# Voicecard-SMRMU-v01.net
KiCad netlist of a schematic drawn in EAGLE
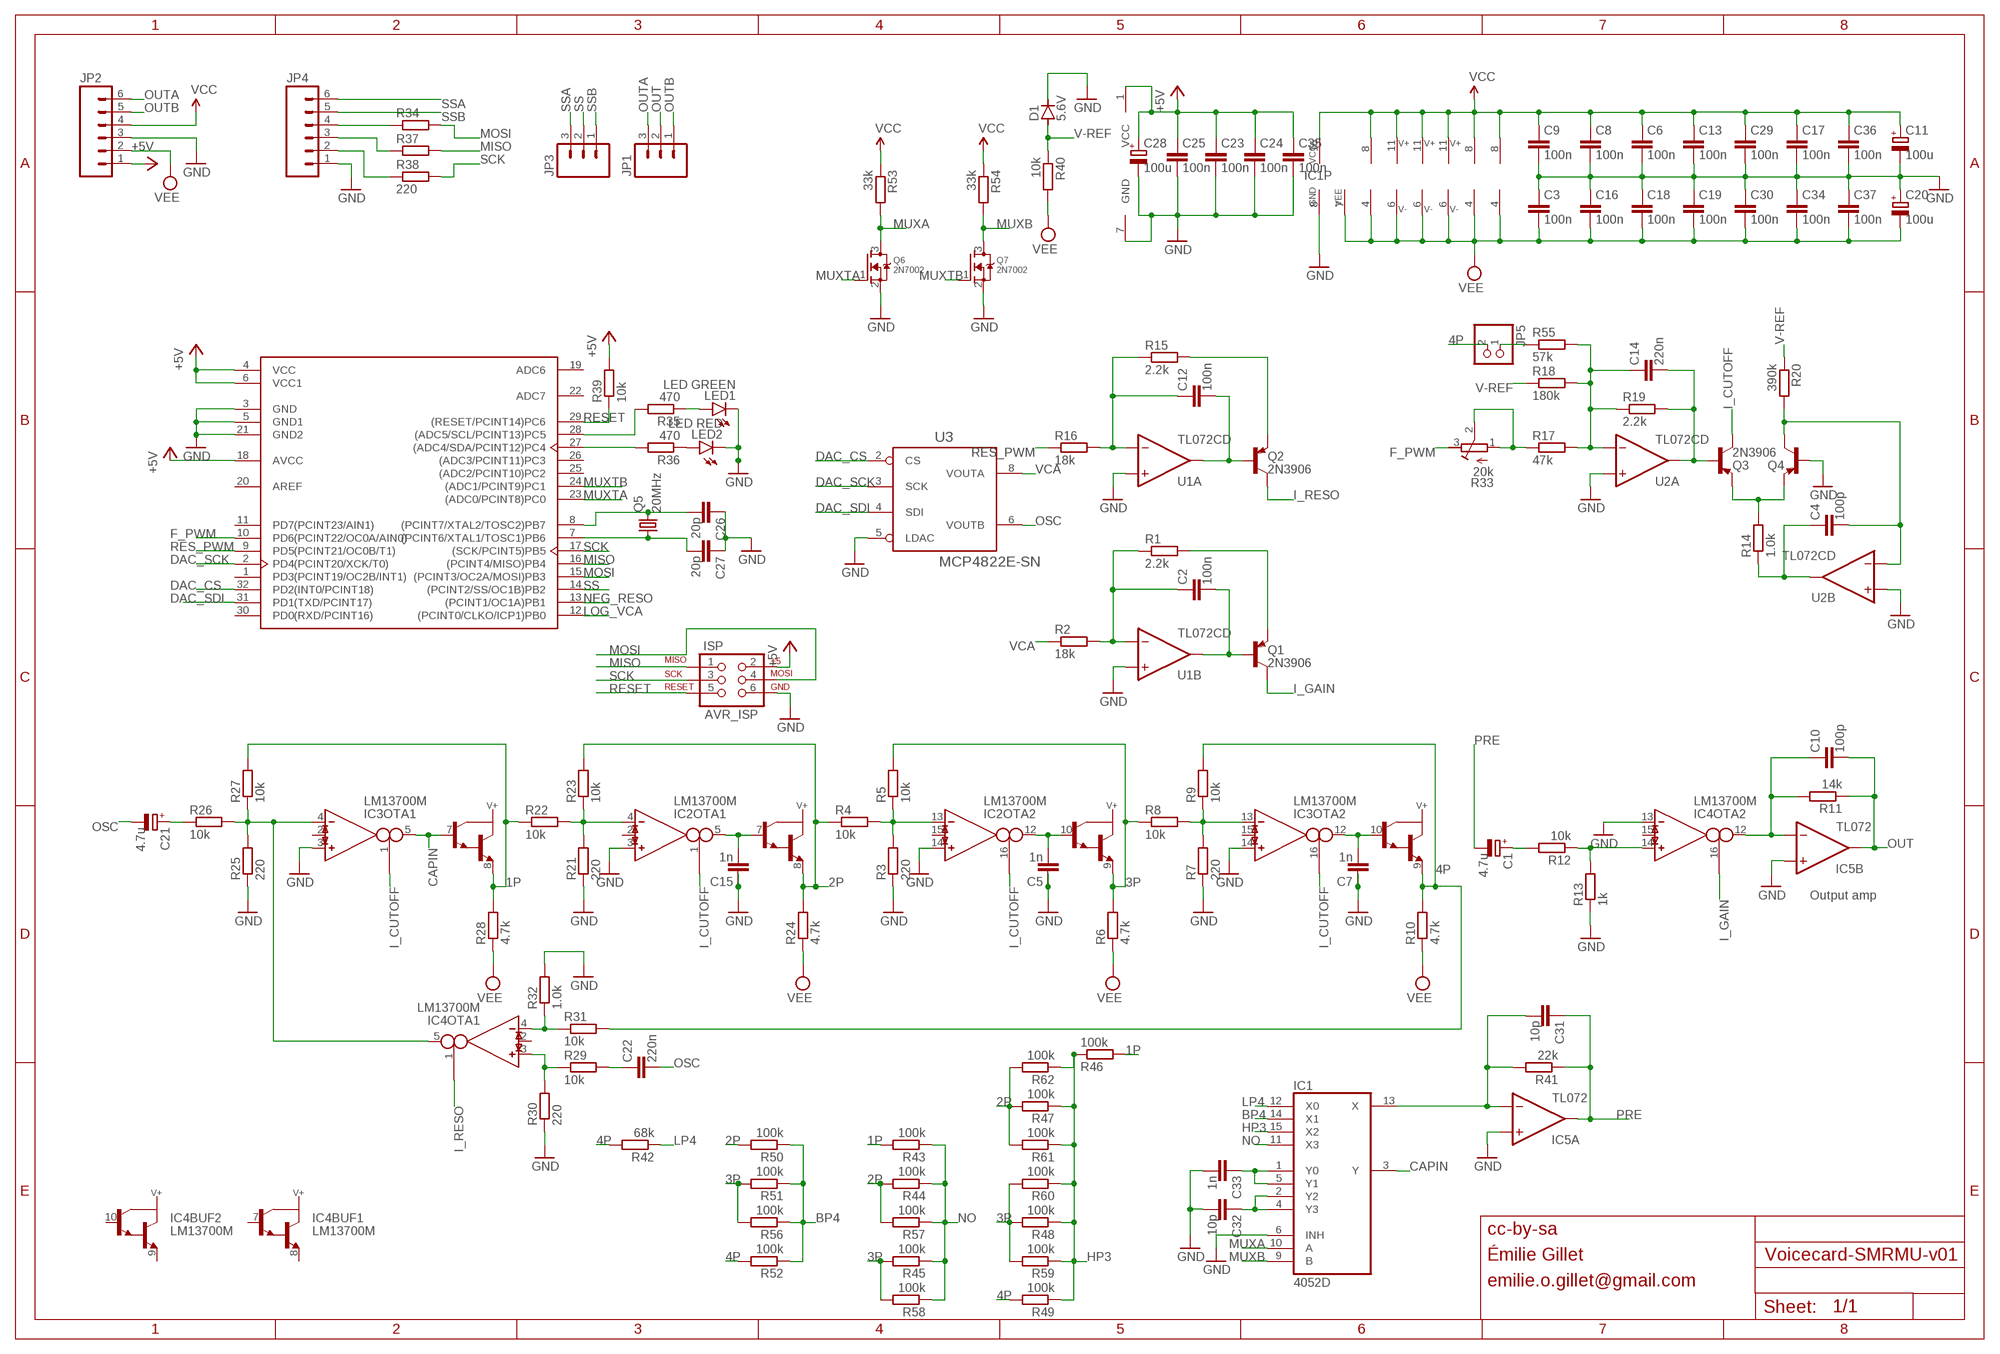
[diagram p0: schematic, sheet 1]

(export (version "E")
  (design (tool "Eeschema 10.0.6"))
  (components
    (comp (ref "C1")
      (value "4.7u")
      (footprint "eagle-import:UD-5X5,8_NICHICON")
      (libsource (lib "eagle-import") (part "CPOL-EUUD-5X5,8"))
    )
    (comp (ref "C2")
      (value "100n")
      (footprint "eagle-import:C0603")
      (libsource (lib "eagle-import") (part "C-EUC0603"))
    )
    (comp (ref "C3")
      (value "100n")
      (footprint "eagle-import:C0603")
      (libsource (lib "eagle-import") (part "C-EUC0603"))
    )
    (comp (ref "C4")
      (value "100p")
      (footprint "eagle-import:C0603")
      (libsource (lib "eagle-import") (part "C-EUC0603"))
    )
    (comp (ref "C5")
      (value "1n")
      (footprint "eagle-import:C0603")
      (libsource (lib "eagle-import") (part "C-EUC0603"))
    )
    (comp (ref "C6")
      (value "100n")
      (footprint "eagle-import:C0603")
      (libsource (lib "eagle-import") (part "C-EUC0603"))
    )
    (comp (ref "C7")
      (value "1n")
      (footprint "eagle-import:C0603")
      (libsource (lib "eagle-import") (part "C-EUC0603"))
    )
    (comp (ref "C8")
      (value "100n")
      (footprint "eagle-import:C0603")
      (libsource (lib "eagle-import") (part "C-EUC0603"))
    )
    (comp (ref "C9")
      (value "100n")
      (footprint "eagle-import:C0603")
      (libsource (lib "eagle-import") (part "C-EUC0603"))
    )
    (comp (ref "C10")
      (value "100p")
      (footprint "eagle-import:C0603")
      (libsource (lib "eagle-import") (part "C-EUC0603"))
    )
    (comp (ref "C11")
      (value "100u")
      (footprint "eagle-import:UD-6,3X7,7_NICHICON")
      (libsource (lib "eagle-import") (part "CPOL-EUUD-6,3X7,7"))
    )
    (comp (ref "C12")
      (value "100n")
      (footprint "eagle-import:C0603")
      (libsource (lib "eagle-import") (part "C-EUC0603"))
    )
    (comp (ref "C13")
      (value "100n")
      (footprint "eagle-import:C0603")
      (libsource (lib "eagle-import") (part "C-EUC0603"))
    )
    (comp (ref "C14")
      (value "220n")
      (footprint "eagle-import:C0603")
      (libsource (lib "eagle-import") (part "C-EUC0603"))
    )
    (comp (ref "C15")
      (value "1n")
      (footprint "eagle-import:C0603")
      (libsource (lib "eagle-import") (part "C-EUC0603"))
    )
    (comp (ref "C16")
      (value "100n")
      (footprint "eagle-import:C0603")
      (libsource (lib "eagle-import") (part "C-EUC0603"))
    )
    (comp (ref "C17")
      (value "100n")
      (footprint "eagle-import:C0603")
      (libsource (lib "eagle-import") (part "C-EUC0603"))
    )
    (comp (ref "C18")
      (value "100n")
      (footprint "eagle-import:C0603")
      (libsource (lib "eagle-import") (part "C-EUC0603"))
    )
    (comp (ref "C19")
      (value "100n")
      (footprint "eagle-import:C0603")
      (libsource (lib "eagle-import") (part "C-EUC0603"))
    )
    (comp (ref "C20")
      (value "100u")
      (footprint "eagle-import:UD-6,3X7,7_NICHICON")
      (libsource (lib "eagle-import") (part "CPOL-EUUD-6,3X7,7"))
    )
    (comp (ref "C21")
      (value "4.7u")
      (footprint "eagle-import:UD-5X5,8_NICHICON")
      (libsource (lib "eagle-import") (part "CPOL-EUUD-5X5,8"))
    )
    (comp (ref "C22")
      (value "220n")
      (footprint "eagle-import:C0603")
      (libsource (lib "eagle-import") (part "C-EUC0603"))
    )
    (comp (ref "C23")
      (value "100n")
      (footprint "eagle-import:C0603")
      (libsource (lib "eagle-import") (part "C-EUC0603"))
    )
    (comp (ref "C24")
      (value "100n")
      (footprint "eagle-import:C0603")
      (libsource (lib "eagle-import") (part "C-EUC0603"))
    )
    (comp (ref "C25")
      (value "100n")
      (footprint "eagle-import:C0603")
      (libsource (lib "eagle-import") (part "C-EUC0603"))
    )
    (comp (ref "C26")
      (value "20p")
      (footprint "eagle-import:C0603")
      (libsource (lib "eagle-import") (part "C-EUC0603"))
    )
    (comp (ref "C27")
      (value "20p")
      (footprint "eagle-import:C0603")
      (libsource (lib "eagle-import") (part "C-EUC0603"))
    )
    (comp (ref "C28")
      (value "100u")
      (footprint "eagle-import:UD-6,3X7,7_NICHICON")
      (libsource (lib "eagle-import") (part "CPOL-EUUD-6,3X7,7"))
    )
    (comp (ref "C29")
      (value "100n")
      (footprint "eagle-import:C0603")
      (libsource (lib "eagle-import") (part "C-EUC0603"))
    )
    (comp (ref "C30")
      (value "100n")
      (footprint "eagle-import:C0603")
      (libsource (lib "eagle-import") (part "C-EUC0603"))
    )
    (comp (ref "C31")
      (value "10p")
      (footprint "eagle-import:C0603")
      (libsource (lib "eagle-import") (part "C-EUC0603"))
    )
    (comp (ref "C32")
      (value "10p")
      (footprint "eagle-import:C0603")
      (libsource (lib "eagle-import") (part "C-EUC0603"))
    )
    (comp (ref "C33")
      (value "1n")
      (footprint "eagle-import:C0603")
      (libsource (lib "eagle-import") (part "C-EUC0603"))
    )
    (comp (ref "C34")
      (value "100n")
      (footprint "eagle-import:C0603")
      (libsource (lib "eagle-import") (part "C-EUC0603"))
    )
    (comp (ref "C35")
      (value "100n")
      (footprint "eagle-import:C0603")
      (libsource (lib "eagle-import") (part "C-EUC0603"))
    )
    (comp (ref "C36")
      (value "100n")
      (footprint "eagle-import:C0603")
      (libsource (lib "eagle-import") (part "C-EUC0603"))
    )
    (comp (ref "C37")
      (value "100n")
      (footprint "eagle-import:C0603")
      (libsource (lib "eagle-import") (part "C-EUC0603"))
    )
    (comp (ref "D1")
      (value "5.6V")
      (footprint "eagle-import:MELF-MLL34")
      (libsource (lib "eagle-import") (part "DIODE-LL-34"))
    )
    (comp (ref "IC1")
      (value "4052D")
      (footprint "eagle-import:SOIC16N")
      (libsource (lib "eagle-import") (part "4052D"))
    )
    (comp (ref "IC2")
      (value "LM13700M")
      (footprint "eagle-import:SO16")
      (libsource (lib "eagle-import") (part "LM13700M"))
    )
    (comp (ref "IC3")
      (value "LM13700M")
      (footprint "eagle-import:SO16")
      (libsource (lib "eagle-import") (part "LM13700M"))
    )
    (comp (ref "IC4")
      (value "LM13700M")
      (footprint "eagle-import:SO16")
      (libsource (lib "eagle-import") (part "LM13700M"))
    )
    (comp (ref "IC5")
      (value "TL072")
      (footprint "eagle-import:SOIC8")
      (libsource (lib "eagle-import") (part "TL072DC"))
    )
    (comp (ref "ISP")
      (value "AVR_ISP")
      (footprint "eagle-import:2X3")
      (libsource (lib "eagle-import") (part "AVR_SPI_PRG_6PTH"))
    )
    (comp (ref "JP1")
      (value "M03PTH")
      (footprint "eagle-import:1X03")
      (libsource (lib "eagle-import") (part "M03PTH"))
    )
    (comp (ref "JP2")
      (value "M06SIP")
      (footprint "eagle-import:1X06")
      (libsource (lib "eagle-import") (part "M06SIP"))
    )
    (comp (ref "JP3")
      (value "M03PTH")
      (footprint "eagle-import:1X03")
      (libsource (lib "eagle-import") (part "M03PTH"))
    )
    (comp (ref "JP4")
      (value "M06SIP")
      (footprint "eagle-import:1X06")
      (libsource (lib "eagle-import") (part "M06SIP"))
    )
    (comp (ref "JP5")
      (value "PINHD-1X2")
      (footprint "eagle-import:1X02")
      (libsource (lib "eagle-import") (part "PINHD-1X2"))
    )
    (comp (ref "LED1")
      (value "LED GREEN")
      (footprint "eagle-import:CHIP-LED0603")
      (libsource (lib "eagle-import") (part "LEDCHIP-LED0603"))
    )
    (comp (ref "LED2")
      (value "LED RED")
      (footprint "eagle-import:CHIP-LED0603")
      (libsource (lib "eagle-import") (part "LEDCHIP-LED0603"))
    )
    (comp (ref "Q1")
      (value "2N3906")
      (footprint "eagle-import:SOT23-BEC")
      (libsource (lib "eagle-import") (part "-PNP-SOT23-BECMMBT3906LT1"))
    )
    (comp (ref "Q2")
      (value "2N3906")
      (footprint "eagle-import:SOT23-BEC")
      (libsource (lib "eagle-import") (part "-PNP-SOT23-BECMMBT3906LT1"))
    )
    (comp (ref "Q3")
      (value "2N3906")
      (footprint "eagle-import:SOT23-BEC")
      (libsource (lib "eagle-import") (part "-PNP-SOT23-BECMMBT3906LT1"))
    )
    (comp (ref "Q4")
      (value "2N3906")
      (footprint "eagle-import:SOT23-BEC")
      (libsource (lib "eagle-import") (part "-PNP-SOT23-BECMMBT3906LT1"))
    )
    (comp (ref "Q5")
      (value "20MHz")
      (footprint "eagle-import:HC49UP")
      (libsource (lib "eagle-import") (part "CRYSTALHC49UP"))
    )
    (comp (ref "Q6")
      (value "2N7002")
      (footprint "eagle-import:SOT23")
      (libsource (lib "eagle-import") (part "MOSFET-NREFLOW"))
    )
    (comp (ref "Q7")
      (value "2N7002")
      (footprint "eagle-import:SOT23")
      (libsource (lib "eagle-import") (part "MOSFET-NREFLOW"))
    )
    (comp (ref "R1")
      (value "2.2k")
      (footprint "eagle-import:R0603")
      (libsource (lib "eagle-import") (part "R-EU_R0603"))
    )
    (comp (ref "R2")
      (value "18k")
      (footprint "eagle-import:R0603")
      (libsource (lib "eagle-import") (part "R-EU_R0603"))
    )
    (comp (ref "R3")
      (value "220")
      (footprint "eagle-import:R0603")
      (libsource (lib "eagle-import") (part "R-EU_R0603"))
    )
    (comp (ref "R4")
      (value "10k")
      (footprint "eagle-import:R0603")
      (libsource (lib "eagle-import") (part "R-EU_R0603"))
    )
    (comp (ref "R5")
      (value "10k")
      (footprint "eagle-import:R0603")
      (libsource (lib "eagle-import") (part "R-EU_R0603"))
    )
    (comp (ref "R6")
      (value "4.7k")
      (footprint "eagle-import:R0603")
      (libsource (lib "eagle-import") (part "R-EU_R0603"))
    )
    (comp (ref "R7")
      (value "220")
      (footprint "eagle-import:R0603")
      (libsource (lib "eagle-import") (part "R-EU_R0603"))
    )
    (comp (ref "R8")
      (value "10k")
      (footprint "eagle-import:R0603")
      (libsource (lib "eagle-import") (part "R-EU_R0603"))
    )
    (comp (ref "R9")
      (value "10k")
      (footprint "eagle-import:R0603")
      (libsource (lib "eagle-import") (part "R-EU_R0603"))
    )
    (comp (ref "R10")
      (value "4.7k")
      (footprint "eagle-import:R0603")
      (libsource (lib "eagle-import") (part "R-EU_R0603"))
    )
    (comp (ref "R11")
      (value "14k")
      (footprint "eagle-import:R0603")
      (libsource (lib "eagle-import") (part "R-EU_R0603"))
    )
    (comp (ref "R12")
      (value "10k")
      (footprint "eagle-import:R0603")
      (libsource (lib "eagle-import") (part "R-EU_R0603"))
    )
    (comp (ref "R13")
      (value "1k")
      (footprint "eagle-import:R0603")
      (libsource (lib "eagle-import") (part "R-EU_R0603"))
    )
    (comp (ref "R14")
      (value "1.0k")
      (footprint "eagle-import:R0603")
      (libsource (lib "eagle-import") (part "R-EU_R0603"))
    )
    (comp (ref "R15")
      (value "2.2k")
      (footprint "eagle-import:R0603")
      (libsource (lib "eagle-import") (part "R-EU_R0603"))
    )
    (comp (ref "R16")
      (value "18k")
      (footprint "eagle-import:R0603")
      (libsource (lib "eagle-import") (part "R-EU_R0603"))
    )
    (comp (ref "R17")
      (value "47k")
      (footprint "eagle-import:R0603")
      (libsource (lib "eagle-import") (part "R-EU_R0603"))
    )
    (comp (ref "R18")
      (value "180k")
      (footprint "eagle-import:R0603")
      (libsource (lib "eagle-import") (part "R-EU_R0603"))
    )
    (comp (ref "R19")
      (value "2.2k")
      (footprint "eagle-import:R0603")
      (libsource (lib "eagle-import") (part "R-EU_R0603"))
    )
    (comp (ref "R20")
      (value "390k")
      (footprint "eagle-import:R0603")
      (libsource (lib "eagle-import") (part "R-EU_R0603"))
    )
    (comp (ref "R21")
      (value "220")
      (footprint "eagle-import:R0603")
      (libsource (lib "eagle-import") (part "R-EU_R0603"))
    )
    (comp (ref "R22")
      (value "10k")
      (footprint "eagle-import:R0603")
      (libsource (lib "eagle-import") (part "R-EU_R0603"))
    )
    (comp (ref "R23")
      (value "10k")
      (footprint "eagle-import:R0603")
      (libsource (lib "eagle-import") (part "R-EU_R0603"))
    )
    (comp (ref "R24")
      (value "4.7k")
      (footprint "eagle-import:R0603")
      (libsource (lib "eagle-import") (part "R-EU_R0603"))
    )
    (comp (ref "R25")
      (value "220")
      (footprint "eagle-import:R0603")
      (libsource (lib "eagle-import") (part "R-EU_R0603"))
    )
    (comp (ref "R26")
      (value "10k")
      (footprint "eagle-import:R0603")
      (libsource (lib "eagle-import") (part "R-EU_R0603"))
    )
    (comp (ref "R27")
      (value "10k")
      (footprint "eagle-import:R0603")
      (libsource (lib "eagle-import") (part "R-EU_R0603"))
    )
    (comp (ref "R28")
      (value "4.7k")
      (footprint "eagle-import:R0603")
      (libsource (lib "eagle-import") (part "R-EU_R0603"))
    )
    (comp (ref "R29")
      (value "10k")
      (footprint "eagle-import:R0603")
      (libsource (lib "eagle-import") (part "R-EU_R0603"))
    )
    (comp (ref "R30")
      (value "220")
      (footprint "eagle-import:R0603")
      (libsource (lib "eagle-import") (part "R-EU_R0603"))
    )
    (comp (ref "R31")
      (value "10k")
      (footprint "eagle-import:R0603")
      (libsource (lib "eagle-import") (part "R-EU_R0603"))
    )
    (comp (ref "R32")
      (value "1.0k")
      (footprint "eagle-import:R0603")
      (libsource (lib "eagle-import") (part "R-EU_R0603"))
    )
    (comp (ref "R33")
      (value "20k")
      (footprint "eagle-import:RTRIM3296P")
      (libsource (lib "eagle-import") (part "R-TRIMM3296P"))
    )
    (comp (ref "R34")
      (value "220")
      (footprint "eagle-import:R0603")
      (libsource (lib "eagle-import") (part "R-EU_R0603"))
    )
    (comp (ref "R35")
      (value "470")
      (footprint "eagle-import:R0603")
      (libsource (lib "eagle-import") (part "R-EU_R0603"))
    )
    (comp (ref "R36")
      (value "470")
      (footprint "eagle-import:R0603")
      (libsource (lib "eagle-import") (part "R-EU_R0603"))
    )
    (comp (ref "R37")
      (value "220")
      (footprint "eagle-import:R0603")
      (libsource (lib "eagle-import") (part "R-EU_R0603"))
    )
    (comp (ref "R38")
      (value "220")
      (footprint "eagle-import:R0603")
      (libsource (lib "eagle-import") (part "R-EU_R0603"))
    )
    (comp (ref "R39")
      (value "10k")
      (footprint "eagle-import:R0603")
      (libsource (lib "eagle-import") (part "R-EU_R0603"))
    )
    (comp (ref "R40")
      (value "10k")
      (footprint "eagle-import:R0603")
      (libsource (lib "eagle-import") (part "R-EU_R0603"))
    )
    (comp (ref "R41")
      (value "22k")
      (footprint "eagle-import:R0603")
      (libsource (lib "eagle-import") (part "R-EU_R0603"))
    )
    (comp (ref "R42")
      (value "68k")
      (footprint "eagle-import:R0603")
      (libsource (lib "eagle-import") (part "R-EU_R0603"))
    )
    (comp (ref "R43")
      (value "100k")
      (footprint "eagle-import:R0603")
      (libsource (lib "eagle-import") (part "R-EU_R0603"))
    )
    (comp (ref "R44")
      (value "100k")
      (footprint "eagle-import:R0603")
      (libsource (lib "eagle-import") (part "R-EU_R0603"))
    )
    (comp (ref "R45")
      (value "100k")
      (footprint "eagle-import:R0603")
      (libsource (lib "eagle-import") (part "R-EU_R0603"))
    )
    (comp (ref "R46")
      (value "100k")
      (footprint "eagle-import:R0603")
      (libsource (lib "eagle-import") (part "R-EU_R0603"))
    )
    (comp (ref "R47")
      (value "100k")
      (footprint "eagle-import:R0603")
      (libsource (lib "eagle-import") (part "R-EU_R0603"))
    )
    (comp (ref "R48")
      (value "100k")
      (footprint "eagle-import:R0603")
      (libsource (lib "eagle-import") (part "R-EU_R0603"))
    )
    (comp (ref "R49")
      (value "100k")
      (footprint "eagle-import:R0603")
      (libsource (lib "eagle-import") (part "R-EU_R0603"))
    )
    (comp (ref "R50")
      (value "100k")
      (footprint "eagle-import:R0603")
      (libsource (lib "eagle-import") (part "R-EU_R0603"))
    )
    (comp (ref "R51")
      (value "100k")
      (footprint "eagle-import:R0603")
      (libsource (lib "eagle-import") (part "R-EU_R0603"))
    )
    (comp (ref "R52")
      (value "100k")
      (footprint "eagle-import:R0603")
      (libsource (lib "eagle-import") (part "R-EU_R0603"))
    )
    (comp (ref "R53")
      (value "33k")
      (footprint "eagle-import:R0603")
      (libsource (lib "eagle-import") (part "R-EU_R0603"))
    )
    (comp (ref "R54")
      (value "33k")
      (footprint "eagle-import:R0603")
      (libsource (lib "eagle-import") (part "R-EU_R0603"))
    )
    (comp (ref "R55")
      (value "57k")
      (footprint "eagle-import:R0603")
      (libsource (lib "eagle-import") (part "R-EU_R0603"))
    )
    (comp (ref "R56")
      (value "100k")
      (footprint "eagle-import:R0603")
      (libsource (lib "eagle-import") (part "R-EU_R0603"))
    )
    (comp (ref "R57")
      (value "100k")
      (footprint "eagle-import:R0603")
      (libsource (lib "eagle-import") (part "R-EU_R0603"))
    )
    (comp (ref "R58")
      (value "100k")
      (footprint "eagle-import:R0603")
      (libsource (lib "eagle-import") (part "R-EU_R0603"))
    )
    (comp (ref "R59")
      (value "100k")
      (footprint "eagle-import:R0603")
      (libsource (lib "eagle-import") (part "R-EU_R0603"))
    )
    (comp (ref "R60")
      (value "100k")
      (footprint "eagle-import:R0603")
      (libsource (lib "eagle-import") (part "R-EU_R0603"))
    )
    (comp (ref "R61")
      (value "100k")
      (footprint "eagle-import:R0603")
      (libsource (lib "eagle-import") (part "R-EU_R0603"))
    )
    (comp (ref "R62")
      (value "100k")
      (footprint "eagle-import:R0603")
      (libsource (lib "eagle-import") (part "R-EU_R0603"))
    )
    (comp (ref "U1")
      (value "TL072CD")
      (footprint "eagle-import:SOIC8")
      (libsource (lib "eagle-import") (part "TL072DC"))
    )
    (comp (ref "U2")
      (value "TL072CD")
      (footprint "eagle-import:SOIC8")
      (libsource (lib "eagle-import") (part "TL072DC"))
    )
    (comp (ref "U3")
      (value "MCP4822E-SN")
      (footprint "eagle-import:SOIC8")
      (libsource (lib "eagle-import") (part "MCP482E-SN2"))
    )
    (comp (ref "U4")
      (value "ATMEGA328P-AU")
      (footprint "eagle-import:TQFP-32")
      (fields
        (field (name "DIGIKEY_PART_NUMBER") "ATMEGA328P-AU-ND")
        (field (name "MANUFACTURER") "Microchip Technology")
        (field (name "CREATED_BY") "PCBLayout.com")
      )
      (libsource (lib "eagle-import") (part "ATMEGA328P-AU"))
    )
  )
  (nets
    (net (code "1") (name "+5V") (class "Default")
      (node (ref "C23") (pin "1") (pinfunction "1_1") (pintype "passive"))
      (node (ref "C24") (pin "1") (pinfunction "1_1") (pintype "passive"))
      (node (ref "C25") (pin "1") (pinfunction "1_1") (pintype "passive"))
      (node (ref "C28") (pin "+") (pinfunction "+_+") (pintype "passive"))
      (node (ref "C35") (pin "1") (pinfunction "1_1") (pintype "passive"))
      (node (ref "ISP") (pin "2") (pinfunction "2_2") (pintype "passive"))
      (node (ref "JP2") (pin "1") (pinfunction "1_1") (pintype "passive"))
      (node (ref "R39") (pin "2") (pinfunction "2_2") (pintype "passive"))
      (node (ref "U3") (pin "1") (pinfunction "VCC_1") (pintype "power_in"))
      (node (ref "U4") (pin "18") (pinfunction "AVCC_18") (pintype "power_in"))
      (node (ref "U4") (pin "4") (pinfunction "VCC_4") (pintype "power_in"))
      (node (ref "U4") (pin "6") (pinfunction "VCC1_6") (pintype "power_in"))
    )
    (net (code "2") (name "/1P") (class "Default")
      (node (ref "IC3") (pin "8") (pinfunction "E_8") (pintype "passive"))
      (node (ref "R22") (pin "1") (pinfunction "1_1") (pintype "passive"))
      (node (ref "R27") (pin "2") (pinfunction "2_2") (pintype "passive"))
      (node (ref "R28") (pin "2") (pinfunction "2_2") (pintype "passive"))
      (node (ref "R43") (pin "2") (pinfunction "2_2") (pintype "passive"))
      (node (ref "R46") (pin "2") (pinfunction "2_2") (pintype "passive"))
    )
    (net (code "3") (name "/2P") (class "Default")
      (node (ref "IC2") (pin "8") (pinfunction "E_8") (pintype "passive"))
      (node (ref "R23") (pin "2") (pinfunction "2_2") (pintype "passive"))
      (node (ref "R24") (pin "2") (pinfunction "2_2") (pintype "passive"))
      (node (ref "R4") (pin "1") (pinfunction "1_1") (pintype "passive"))
      (node (ref "R44") (pin "2") (pinfunction "2_2") (pintype "passive"))
      (node (ref "R47") (pin "2") (pinfunction "2_2") (pintype "passive"))
      (node (ref "R50") (pin "2") (pinfunction "2_2") (pintype "passive"))
      (node (ref "R57") (pin "2") (pinfunction "2_2") (pintype "passive"))
      (node (ref "R61") (pin "2") (pinfunction "2_2") (pintype "passive"))
      (node (ref "R62") (pin "2") (pinfunction "2_2") (pintype "passive"))
    )
    (net (code "4") (name "/3P") (class "Default")
      (node (ref "IC2") (pin "9") (pinfunction "E_9") (pintype "passive"))
      (node (ref "R45") (pin "2") (pinfunction "2_2") (pintype "passive"))
      (node (ref "R48") (pin "2") (pinfunction "2_2") (pintype "passive"))
      (node (ref "R5") (pin "2") (pinfunction "2_2") (pintype "passive"))
      (node (ref "R51") (pin "2") (pinfunction "2_2") (pintype "passive"))
      (node (ref "R56") (pin "2") (pinfunction "2_2") (pintype "passive"))
      (node (ref "R58") (pin "2") (pinfunction "2_2") (pintype "passive"))
      (node (ref "R59") (pin "2") (pinfunction "2_2") (pintype "passive"))
      (node (ref "R6") (pin "2") (pinfunction "2_2") (pintype "passive"))
      (node (ref "R60") (pin "2") (pinfunction "2_2") (pintype "passive"))
      (node (ref "R8") (pin "1") (pinfunction "1_1") (pintype "passive"))
    )
    (net (code "5") (name "/4P") (class "Default")
      (node (ref "IC3") (pin "9") (pinfunction "E_9") (pintype "passive"))
      (node (ref "JP5") (pin "2") (pinfunction "2_2") (pintype "passive"))
      (node (ref "R10") (pin "2") (pinfunction "2_2") (pintype "passive"))
      (node (ref "R31") (pin "2") (pinfunction "2_2") (pintype "passive"))
      (node (ref "R42") (pin "2") (pinfunction "2_2") (pintype "passive"))
      (node (ref "R49") (pin "2") (pinfunction "2_2") (pintype "passive"))
      (node (ref "R52") (pin "2") (pinfunction "2_2") (pintype "passive"))
      (node (ref "R9") (pin "2") (pinfunction "2_2") (pintype "passive"))
    )
    (net (code "6") (name "/AREF") (class "Default")
      (node (ref "U4") (pin "20") (pinfunction "AREF_20") (pintype "power_in"))
    )
    (net (code "7") (name "/BP4") (class "Default")
      (node (ref "IC1") (pin "14") (pinfunction "X1_14") (pintype "bidirectional"))
      (node (ref "R50") (pin "1") (pinfunction "1_1") (pintype "passive"))
      (node (ref "R51") (pin "1") (pinfunction "1_1") (pintype "passive"))
      (node (ref "R52") (pin "1") (pinfunction "1_1") (pintype "passive"))
      (node (ref "R56") (pin "1") (pinfunction "1_1") (pintype "passive"))
    )
    (net (code "8") (name "/CAPIN") (class "Default")
      (node (ref "IC1") (pin "3") (pinfunction "Y_3") (pintype "bidirectional"))
      (node (ref "IC3") (pin "5") (pinfunction "OUT_5") (pintype "output"))
      (node (ref "IC3") (pin "7") (pinfunction "B_7") (pintype "passive"))
    )
    (net (code "9") (name "/DAC_CS") (class "Default")
      (node (ref "U3") (pin "2") (pinfunction "CS_2") (pintype "input"))
      (node (ref "U4") (pin "32") (pinfunction "PD2(INT0/PCINT18)_32") (pintype "bidirectional"))
    )
    (net (code "10") (name "/DAC_SCK") (class "Default")
      (node (ref "U3") (pin "3") (pinfunction "SCK_3") (pintype "input"))
      (node (ref "U4") (pin "2") (pinfunction "PD4(PCINT20/XCK/T0)_2") (pintype "bidirectional"))
    )
    (net (code "11") (name "/DAC_SDI") (class "Default")
      (node (ref "U3") (pin "4") (pinfunction "SDI_4") (pintype "input"))
      (node (ref "U4") (pin "31") (pinfunction "PD1(TXD/PCINT17)_31") (pintype "bidirectional"))
    )
    (net (code "12") (name "/F_PWM") (class "Default")
      (node (ref "R33") (pin "3") (pinfunction "E_3") (pintype "passive"))
      (node (ref "U4") (pin "10") (pinfunction "PD6(PCINT22/OC0A/AIN0)_10") (pintype "bidirectional"))
    )
    (net (code "13") (name "/HP3") (class "Default")
      (node (ref "IC1") (pin "15") (pinfunction "X2_15") (pintype "bidirectional"))
      (node (ref "R46") (pin "1") (pinfunction "1_1") (pintype "passive"))
      (node (ref "R47") (pin "1") (pinfunction "1_1") (pintype "passive"))
      (node (ref "R48") (pin "1") (pinfunction "1_1") (pintype "passive"))
      (node (ref "R49") (pin "1") (pinfunction "1_1") (pintype "passive"))
      (node (ref "R59") (pin "1") (pinfunction "1_1") (pintype "passive"))
      (node (ref "R60") (pin "1") (pinfunction "1_1") (pintype "passive"))
      (node (ref "R61") (pin "1") (pinfunction "1_1") (pintype "passive"))
      (node (ref "R62") (pin "1") (pinfunction "1_1") (pintype "passive"))
    )
    (net (code "14") (name "/I_CUTOFF") (class "Default")
      (node (ref "IC2") (pin "1") (pinfunction "I_BIAS_1") (pintype "input"))
      (node (ref "IC2") (pin "16") (pinfunction "I_BIAS_16") (pintype "input"))
      (node (ref "IC3") (pin "1") (pinfunction "I_BIAS_1") (pintype "input"))
      (node (ref "IC3") (pin "16") (pinfunction "I_BIAS_16") (pintype "input"))
      (node (ref "Q3") (pin "C") (pinfunction "C_C") (pintype "passive"))
    )
    (net (code "15") (name "/I_GAIN") (class "Default")
      (node (ref "IC4") (pin "16") (pinfunction "I_BIAS_16") (pintype "input"))
      (node (ref "Q1") (pin "C") (pinfunction "C_C") (pintype "passive"))
    )
    (net (code "16") (name "/I_RESO") (class "Default")
      (node (ref "IC4") (pin "1") (pinfunction "I_BIAS_1") (pintype "input"))
      (node (ref "Q2") (pin "C") (pinfunction "C_C") (pintype "passive"))
    )
    (net (code "17") (name "/LOG_VCA") (class "Default")
      (node (ref "U4") (pin "12") (pinfunction "(PCINT0/CLKO/ICP1)PB0_12") (pintype "bidirectional"))
    )
    (net (code "18") (name "/LP4") (class "Default")
      (node (ref "IC1") (pin "12") (pinfunction "X0_12") (pintype "bidirectional"))
      (node (ref "R42") (pin "1") (pinfunction "1_1") (pintype "passive"))
    )
    (net (code "19") (name "/MISO") (class "Default")
      (node (ref "ISP") (pin "1") (pinfunction "1_1") (pintype "passive"))
      (node (ref "R37") (pin "2") (pinfunction "2_2") (pintype "passive"))
      (node (ref "U4") (pin "16") (pinfunction "(PCINT4/MISO)PB4_16") (pintype "bidirectional"))
    )
    (net (code "20") (name "/MOSI") (class "Default")
      (node (ref "ISP") (pin "4") (pinfunction "4_4") (pintype "passive"))
      (node (ref "R34") (pin "2") (pinfunction "2_2") (pintype "passive"))
      (node (ref "U4") (pin "15") (pinfunction "(PCINT3/OC2A/MOSI)PB3_15") (pintype "bidirectional"))
    )
    (net (code "21") (name "/MUXA") (class "Default")
      (node (ref "IC1") (pin "10") (pinfunction "A_10") (pintype "input"))
      (node (ref "Q6") (pin "3") (pinfunction "D_3") (pintype "bidirectional"))
      (node (ref "R53") (pin "2") (pinfunction "2_2") (pintype "passive"))
    )
    (net (code "22") (name "/MUXB") (class "Default")
      (node (ref "IC1") (pin "9") (pinfunction "B_9") (pintype "input"))
      (node (ref "Q7") (pin "3") (pinfunction "D_3") (pintype "bidirectional"))
      (node (ref "R54") (pin "2") (pinfunction "2_2") (pintype "passive"))
    )
    (net (code "23") (name "/MUXTA") (class "Default")
      (node (ref "Q6") (pin "1") (pinfunction "G_1") (pintype "bidirectional"))
      (node (ref "U4") (pin "23") (pinfunction "(ADC0/PCINT8)PC0_23") (pintype "bidirectional"))
    )
    (net (code "24") (name "/MUXTB") (class "Default")
      (node (ref "Q7") (pin "1") (pinfunction "G_1") (pintype "bidirectional"))
      (node (ref "U4") (pin "24") (pinfunction "(ADC1/PCINT9)PC1_24") (pintype "bidirectional"))
    )
    (net (code "25") (name "/NEG_RESO") (class "Default")
      (node (ref "U4") (pin "13") (pinfunction "(PCINT1/OC1A)PB1_13") (pintype "bidirectional"))
    )
    (net (code "26") (name "/NO") (class "Default")
      (node (ref "IC1") (pin "11") (pinfunction "X3_11") (pintype "bidirectional"))
      (node (ref "R43") (pin "1") (pinfunction "1_1") (pintype "passive"))
      (node (ref "R44") (pin "1") (pinfunction "1_1") (pintype "passive"))
      (node (ref "R45") (pin "1") (pinfunction "1_1") (pintype "passive"))
      (node (ref "R57") (pin "1") (pinfunction "1_1") (pintype "passive"))
      (node (ref "R58") (pin "1") (pinfunction "1_1") (pintype "passive"))
    )
    (net (code "27") (name "/OSC") (class "Default")
      (node (ref "C21") (pin "-") (pinfunction "-_-") (pintype "passive"))
      (node (ref "C22") (pin "2") (pinfunction "2_2") (pintype "passive"))
      (node (ref "U3") (pin "6") (pinfunction "VOUTB_6") (pintype "output"))
    )
    (net (code "28") (name "/OUT") (class "Default")
      (node (ref "C10") (pin "2") (pinfunction "2_2") (pintype "passive"))
      (node (ref "IC5") (pin "7") (pinfunction "OUT_7") (pintype "output"))
      (node (ref "JP1") (pin "2") (pinfunction "2_2") (pintype "passive"))
      (node (ref "R11") (pin "1") (pinfunction "1_1") (pintype "passive"))
    )
    (net (code "29") (name "/OUTA") (class "Default")
      (node (ref "JP1") (pin "3") (pinfunction "3_3") (pintype "passive"))
      (node (ref "JP2") (pin "6") (pinfunction "6_6") (pintype "passive"))
    )
    (net (code "30") (name "/OUTB") (class "Default")
      (node (ref "JP1") (pin "1") (pinfunction "1_1") (pintype "passive"))
      (node (ref "JP2") (pin "5") (pinfunction "5_5") (pintype "passive"))
    )
    (net (code "31") (name "/PRE") (class "Default")
      (node (ref "C1") (pin "-") (pinfunction "-_-") (pintype "passive"))
      (node (ref "C31") (pin "1") (pinfunction "1_1") (pintype "passive"))
      (node (ref "IC5") (pin "1") (pinfunction "OUT_1") (pintype "output"))
      (node (ref "R41") (pin "1") (pinfunction "1_1") (pintype "passive"))
    )
    (net (code "32") (name "/RESET") (class "Default")
      (node (ref "ISP") (pin "5") (pinfunction "5_5") (pintype "passive"))
      (node (ref "R39") (pin "1") (pinfunction "1_1") (pintype "passive"))
      (node (ref "U4") (pin "29") (pinfunction "(RESET/PCINT14)PC6_29") (pintype "bidirectional"))
    )
    (net (code "33") (name "/RES_PWM") (class "Default")
      (node (ref "R16") (pin "1") (pinfunction "1_1") (pintype "passive"))
      (node (ref "U4") (pin "9") (pinfunction "PD5(PCINT21/OC0B/T1)_9") (pintype "bidirectional"))
    )
    (net (code "34") (name "/SCK") (class "Default")
      (node (ref "ISP") (pin "3") (pinfunction "3_3") (pintype "passive"))
      (node (ref "R38") (pin "2") (pinfunction "2_2") (pintype "passive"))
      (node (ref "U4") (pin "17") (pinfunction "(SCK/PCINT5)PB5_17") (pintype "bidirectional"))
    )
    (net (code "35") (name "/SS") (class "Default")
      (node (ref "JP3") (pin "2") (pinfunction "2_2") (pintype "passive"))
      (node (ref "U4") (pin "14") (pinfunction "(PCINT2/SS/OC1B)PB2_14") (pintype "bidirectional"))
    )
    (net (code "36") (name "/SSA") (class "Default")
      (node (ref "JP3") (pin "3") (pinfunction "3_3") (pintype "passive"))
      (node (ref "JP4") (pin "6") (pinfunction "6_6") (pintype "passive"))
    )
    (net (code "37") (name "/SSB") (class "Default")
      (node (ref "JP3") (pin "1") (pinfunction "1_1") (pintype "passive"))
      (node (ref "JP4") (pin "5") (pinfunction "5_5") (pintype "passive"))
    )
    (net (code "38") (name "/V-REF") (class "Default")
      (node (ref "D1") (pin "2") (pinfunction "A_2") (pintype "passive"))
      (node (ref "R18") (pin "1") (pinfunction "1_1") (pintype "passive"))
      (node (ref "R20") (pin "1") (pinfunction "1_1") (pintype "passive"))
      (node (ref "R40") (pin "1") (pinfunction "1_1") (pintype "passive"))
    )
    (net (code "39") (name "/VCA") (class "Default")
      (node (ref "R2") (pin "1") (pinfunction "1_1") (pintype "passive"))
      (node (ref "U3") (pin "8") (pinfunction "VOUTA_8") (pintype "output"))
    )
    (net (code "40") (name "GND") (class "Default")
      (node (ref "C11") (pin "-") (pinfunction "-_-") (pintype "passive"))
      (node (ref "C13") (pin "2") (pinfunction "2_2") (pintype "passive"))
      (node (ref "C15") (pin "1") (pinfunction "1_1") (pintype "passive"))
      (node (ref "C16") (pin "1") (pinfunction "1_1") (pintype "passive"))
      (node (ref "C17") (pin "2") (pinfunction "2_2") (pintype "passive"))
      (node (ref "C18") (pin "1") (pinfunction "1_1") (pintype "passive"))
      (node (ref "C19") (pin "1") (pinfunction "1_1") (pintype "passive"))
      (node (ref "C20") (pin "+") (pinfunction "+_+") (pintype "passive"))
      (node (ref "C23") (pin "2") (pinfunction "2_2") (pintype "passive"))
      (node (ref "C24") (pin "2") (pinfunction "2_2") (pintype "passive"))
      (node (ref "C25") (pin "2") (pinfunction "2_2") (pintype "passive"))
      (node (ref "C26") (pin "1") (pinfunction "1_1") (pintype "passive"))
      (node (ref "C27") (pin "1") (pinfunction "1_1") (pintype "passive"))
      (node (ref "C28") (pin "-") (pinfunction "-_-") (pintype "passive"))
      (node (ref "C29") (pin "2") (pinfunction "2_2") (pintype "passive"))
      (node (ref "C3") (pin "1") (pinfunction "1_1") (pintype "passive"))
      (node (ref "C30") (pin "1") (pinfunction "1_1") (pintype "passive"))
      (node (ref "C32") (pin "2") (pinfunction "2_2") (pintype "passive"))
      (node (ref "C33") (pin "2") (pinfunction "2_2") (pintype "passive"))
      (node (ref "C34") (pin "1") (pinfunction "1_1") (pintype "passive"))
      (node (ref "C35") (pin "2") (pinfunction "2_2") (pintype "passive"))
      (node (ref "C36") (pin "2") (pinfunction "2_2") (pintype "passive"))
      (node (ref "C37") (pin "1") (pinfunction "1_1") (pintype "passive"))
      (node (ref "C5") (pin "1") (pinfunction "1_1") (pintype "passive"))
      (node (ref "C6") (pin "2") (pinfunction "2_2") (pintype "passive"))
      (node (ref "C7") (pin "1") (pinfunction "1_1") (pintype "passive"))
      (node (ref "C8") (pin "2") (pinfunction "2_2") (pintype "passive"))
      (node (ref "C9") (pin "2") (pinfunction "2_2") (pintype "passive"))
      (node (ref "D1") (pin "1") (pinfunction "C_1") (pintype "passive"))
      (node (ref "IC1") (pin "6") (pinfunction "INH_6") (pintype "input"))
      (node (ref "IC1") (pin "8") (pinfunction "GND_8") (pintype "power_in"))
      (node (ref "IC2") (pin "14") (pinfunction "IN_P_14") (pintype "input"))
      (node (ref "IC2") (pin "3") (pinfunction "IN_P_3") (pintype "input"))
      (node (ref "IC3") (pin "14") (pinfunction "IN_P_14") (pintype "input"))
      (node (ref "IC3") (pin "3") (pinfunction "IN_P_3") (pintype "input"))
      (node (ref "IC4") (pin "13") (pinfunction "IN_N_13") (pintype "input"))
      (node (ref "IC5") (pin "3") (pinfunction "+IN_3") (pintype "input"))
      (node (ref "IC5") (pin "5") (pinfunction "+IN_5") (pintype "input"))
      (node (ref "ISP") (pin "6") (pinfunction "6_6") (pintype "passive"))
      (node (ref "JP2") (pin "3") (pinfunction "3_3") (pintype "passive"))
      (node (ref "JP4") (pin "1") (pinfunction "1_1") (pintype "passive"))
      (node (ref "LED1") (pin "C") (pinfunction "C_C") (pintype "passive"))
      (node (ref "LED2") (pin "C") (pinfunction "C_C") (pintype "passive"))
      (node (ref "Q4") (pin "B") (pinfunction "B_B") (pintype "passive"))
      (node (ref "Q6") (pin "2") (pinfunction "S_2") (pintype "bidirectional"))
      (node (ref "Q7") (pin "2") (pinfunction "S_2") (pintype "bidirectional"))
      (node (ref "R13") (pin "1") (pinfunction "1_1") (pintype "passive"))
      (node (ref "R21") (pin "1") (pinfunction "1_1") (pintype "passive"))
      (node (ref "R25") (pin "1") (pinfunction "1_1") (pintype "passive"))
      (node (ref "R3") (pin "1") (pinfunction "1_1") (pintype "passive"))
      (node (ref "R30") (pin "1") (pinfunction "1_1") (pintype "passive"))
      (node (ref "R32") (pin "2") (pinfunction "2_2") (pintype "passive"))
      (node (ref "R7") (pin "1") (pinfunction "1_1") (pintype "passive"))
      (node (ref "U1") (pin "3") (pinfunction "+IN_3") (pintype "input"))
      (node (ref "U1") (pin "5") (pinfunction "+IN_5") (pintype "input"))
      (node (ref "U2") (pin "3") (pinfunction "+IN_3") (pintype "input"))
      (node (ref "U2") (pin "5") (pinfunction "+IN_5") (pintype "input"))
      (node (ref "U3") (pin "5") (pinfunction "LDAC_5") (pintype "input"))
      (node (ref "U3") (pin "7") (pinfunction "GND_7") (pintype "power_in"))
      (node (ref "U4") (pin "21") (pinfunction "GND2_21") (pintype "power_in"))
      (node (ref "U4") (pin "3") (pinfunction "GND_3") (pintype "power_in"))
      (node (ref "U4") (pin "5") (pinfunction "GND1_5") (pintype "power_in"))
    )
    (net (code "41") (name "Net-(C1-Pad+)") (class "Default")
      (node (ref "C1") (pin "+") (pinfunction "+_+") (pintype "passive"))
      (node (ref "R12") (pin "2") (pinfunction "2_2") (pintype "passive"))
    )
    (net (code "42") (name "Net-(C21-Pad+)") (class "Default")
      (node (ref "C21") (pin "+") (pinfunction "+_+") (pintype "passive"))
      (node (ref "R26") (pin "1") (pinfunction "1_1") (pintype "passive"))
    )
    (net (code "43") (name "Net-(C22-Pad1)") (class "Default")
      (node (ref "C22") (pin "1") (pinfunction "1_1") (pintype "passive"))
      (node (ref "R29") (pin "2") (pinfunction "2_2") (pintype "passive"))
    )
    (net (code "44") (name "Net-(IC1A-X)") (class "Default")
      (node (ref "C31") (pin "2") (pinfunction "2_2") (pintype "passive"))
      (node (ref "IC1") (pin "13") (pinfunction "X_13") (pintype "bidirectional"))
      (node (ref "IC5") (pin "2") (pinfunction "-IN_2") (pintype "input"))
      (node (ref "R41") (pin "2") (pinfunction "2_2") (pintype "passive"))
    )
    (net (code "45") (name "Net-(IC1A-Y0)") (class "Default")
      (node (ref "C33") (pin "1") (pinfunction "1_1") (pintype "passive"))
      (node (ref "IC1") (pin "1") (pinfunction "Y0_1") (pintype "bidirectional"))
      (node (ref "IC1") (pin "5") (pinfunction "Y1_5") (pintype "bidirectional"))
    )
    (net (code "46") (name "Net-(IC1A-Y2)") (class "Default")
      (node (ref "C32") (pin "1") (pinfunction "1_1") (pintype "passive"))
      (node (ref "IC1") (pin "2") (pinfunction "Y2_2") (pintype "bidirectional"))
      (node (ref "IC1") (pin "4") (pinfunction "Y3_4") (pintype "bidirectional"))
    )
    (net (code "47") (name "Net-(IC2A-B)") (class "Default")
      (node (ref "C15") (pin "2") (pinfunction "2_2") (pintype "passive"))
      (node (ref "IC2") (pin "5") (pinfunction "OUT_5") (pintype "output"))
      (node (ref "IC2") (pin "7") (pinfunction "B_7") (pintype "passive"))
    )
    (net (code "48") (name "Net-(IC2B-B)") (class "Default")
      (node (ref "C5") (pin "2") (pinfunction "2_2") (pintype "passive"))
      (node (ref "IC2") (pin "10") (pinfunction "B_10") (pintype "passive"))
      (node (ref "IC2") (pin "12") (pinfunction "OUT_12") (pintype "output"))
    )
    (net (code "49") (name "Net-(IC2C-IN_N)") (class "Default")
      (node (ref "IC2") (pin "4") (pinfunction "IN_N_4") (pintype "input"))
      (node (ref "R21") (pin "2") (pinfunction "2_2") (pintype "passive"))
      (node (ref "R22") (pin "2") (pinfunction "2_2") (pintype "passive"))
      (node (ref "R23") (pin "1") (pinfunction "1_1") (pintype "passive"))
    )
    (net (code "50") (name "Net-(IC2D-IN_N)") (class "Default")
      (node (ref "IC2") (pin "13") (pinfunction "IN_N_13") (pintype "input"))
      (node (ref "R3") (pin "2") (pinfunction "2_2") (pintype "passive"))
      (node (ref "R4") (pin "2") (pinfunction "2_2") (pintype "passive"))
      (node (ref "R5") (pin "1") (pinfunction "1_1") (pintype "passive"))
    )
    (net (code "51") (name "Net-(IC3B-B)") (class "Default")
      (node (ref "C7") (pin "2") (pinfunction "2_2") (pintype "passive"))
      (node (ref "IC3") (pin "10") (pinfunction "B_10") (pintype "passive"))
      (node (ref "IC3") (pin "12") (pinfunction "OUT_12") (pintype "output"))
    )
    (net (code "52") (name "Net-(IC3C-IN_N)") (class "Default")
      (node (ref "IC3") (pin "4") (pinfunction "IN_N_4") (pintype "input"))
      (node (ref "IC4") (pin "5") (pinfunction "OUT_5") (pintype "output"))
      (node (ref "R25") (pin "2") (pinfunction "2_2") (pintype "passive"))
      (node (ref "R26") (pin "2") (pinfunction "2_2") (pintype "passive"))
      (node (ref "R27") (pin "1") (pinfunction "1_1") (pintype "passive"))
    )
    (net (code "53") (name "Net-(IC3D-IN_N)") (class "Default")
      (node (ref "IC3") (pin "13") (pinfunction "IN_N_13") (pintype "input"))
      (node (ref "R7") (pin "2") (pinfunction "2_2") (pintype "passive"))
      (node (ref "R8") (pin "2") (pinfunction "2_2") (pintype "passive"))
      (node (ref "R9") (pin "1") (pinfunction "1_1") (pintype "passive"))
    )
    (net (code "54") (name "Net-(IC4C-IN_N)") (class "Default")
      (node (ref "IC4") (pin "4") (pinfunction "IN_N_4") (pintype "input"))
      (node (ref "R31") (pin "1") (pinfunction "1_1") (pintype "passive"))
      (node (ref "R32") (pin "1") (pinfunction "1_1") (pintype "passive"))
    )
    (net (code "55") (name "Net-(IC4C-IN_P)") (class "Default")
      (node (ref "IC4") (pin "3") (pinfunction "IN_P_3") (pintype "input"))
      (node (ref "R29") (pin "1") (pinfunction "1_1") (pintype "passive"))
      (node (ref "R30") (pin "2") (pinfunction "2_2") (pintype "passive"))
    )
    (net (code "56") (name "Net-(IC4D-IN_P)") (class "Default")
      (node (ref "IC4") (pin "14") (pinfunction "IN_P_14") (pintype "input"))
      (node (ref "R12") (pin "1") (pinfunction "1_1") (pintype "passive"))
      (node (ref "R13") (pin "2") (pinfunction "2_2") (pintype "passive"))
    )
    (net (code "57") (name "Net-(IC4D-OUT)") (class "Default")
      (node (ref "C10") (pin "1") (pinfunction "1_1") (pintype "passive"))
      (node (ref "IC4") (pin "12") (pinfunction "OUT_12") (pintype "output"))
      (node (ref "IC5") (pin "6") (pinfunction "-IN_6") (pintype "input"))
      (node (ref "R11") (pin "2") (pinfunction "2_2") (pintype "passive"))
    )
    (net (code "58") (name "Net-(JP4-Pad2)") (class "Default")
      (node (ref "JP4") (pin "2") (pinfunction "2_2") (pintype "passive"))
      (node (ref "R38") (pin "1") (pinfunction "1_1") (pintype "passive"))
    )
    (net (code "59") (name "Net-(JP4-Pad3)") (class "Default")
      (node (ref "JP4") (pin "3") (pinfunction "3_3") (pintype "passive"))
      (node (ref "R37") (pin "1") (pinfunction "1_1") (pintype "passive"))
    )
    (net (code "60") (name "Net-(JP4-Pad4)") (class "Default")
      (node (ref "JP4") (pin "4") (pinfunction "4_4") (pintype "passive"))
      (node (ref "R34") (pin "1") (pinfunction "1_1") (pintype "passive"))
    )
    (net (code "61") (name "Net-(JP5-Pad1)") (class "Default")
      (node (ref "JP5") (pin "1") (pinfunction "1_1") (pintype "passive"))
      (node (ref "R55") (pin "1") (pinfunction "1_1") (pintype "passive"))
    )
    (net (code "62") (name "Net-(LED1-PadA)") (class "Default")
      (node (ref "LED1") (pin "A") (pinfunction "A_A") (pintype "passive"))
      (node (ref "R35") (pin "1") (pinfunction "1_1") (pintype "passive"))
    )
    (net (code "63") (name "Net-(LED2-PadA)") (class "Default")
      (node (ref "LED2") (pin "A") (pinfunction "A_A") (pintype "passive"))
      (node (ref "R36") (pin "1") (pinfunction "1_1") (pintype "passive"))
    )
    (net (code "64") (name "Net-(Q1-PadE)") (class "Default")
      (node (ref "Q1") (pin "E") (pinfunction "E_E") (pintype "passive"))
      (node (ref "R1") (pin "2") (pinfunction "2_2") (pintype "passive"))
    )
    (net (code "65") (name "Net-(Q2-PadE)") (class "Default")
      (node (ref "Q2") (pin "E") (pinfunction "E_E") (pintype "passive"))
      (node (ref "R15") (pin "2") (pinfunction "2_2") (pintype "passive"))
    )
    (net (code "66") (name "Net-(Q3-PadE)") (class "Default")
      (node (ref "Q3") (pin "E") (pinfunction "E_E") (pintype "passive"))
      (node (ref "Q4") (pin "E") (pinfunction "E_E") (pintype "passive"))
      (node (ref "R14") (pin "2") (pinfunction "2_2") (pintype "passive"))
    )
    (net (code "67") (name "Net-(R33-A)") (class "Default")
      (node (ref "R17") (pin "1") (pinfunction "1_1") (pintype "passive"))
      (node (ref "R33") (pin "1") (pinfunction "A_1") (pintype "passive"))
      (node (ref "R33") (pin "2") (pinfunction "S_2") (pintype "passive"))
    )
    (net (code "68") (name "Net-(U1A--IN)") (class "Default")
      (node (ref "C12") (pin "1") (pinfunction "1_1") (pintype "passive"))
      (node (ref "R15") (pin "1") (pinfunction "1_1") (pintype "passive"))
      (node (ref "R16") (pin "2") (pinfunction "2_2") (pintype "passive"))
      (node (ref "U1") (pin "2") (pinfunction "-IN_2") (pintype "input"))
    )
    (net (code "69") (name "Net-(U1A-OUT)") (class "Default")
      (node (ref "C12") (pin "2") (pinfunction "2_2") (pintype "passive"))
      (node (ref "Q2") (pin "B") (pinfunction "B_B") (pintype "passive"))
      (node (ref "U1") (pin "1") (pinfunction "OUT_1") (pintype "output"))
    )
    (net (code "70") (name "Net-(U1B--IN)") (class "Default")
      (node (ref "C2") (pin "1") (pinfunction "1_1") (pintype "passive"))
      (node (ref "R1") (pin "1") (pinfunction "1_1") (pintype "passive"))
      (node (ref "R2") (pin "2") (pinfunction "2_2") (pintype "passive"))
      (node (ref "U1") (pin "6") (pinfunction "-IN_6") (pintype "input"))
    )
    (net (code "71") (name "Net-(U1B-OUT)") (class "Default")
      (node (ref "C2") (pin "2") (pinfunction "2_2") (pintype "passive"))
      (node (ref "Q1") (pin "B") (pinfunction "B_B") (pintype "passive"))
      (node (ref "U1") (pin "7") (pinfunction "OUT_7") (pintype "output"))
    )
    (net (code "72") (name "Net-(U2A--IN)") (class "Default")
      (node (ref "C14") (pin "1") (pinfunction "1_1") (pintype "passive"))
      (node (ref "R17") (pin "2") (pinfunction "2_2") (pintype "passive"))
      (node (ref "R18") (pin "2") (pinfunction "2_2") (pintype "passive"))
      (node (ref "R19") (pin "1") (pinfunction "1_1") (pintype "passive"))
      (node (ref "R55") (pin "2") (pinfunction "2_2") (pintype "passive"))
      (node (ref "U2") (pin "2") (pinfunction "-IN_2") (pintype "input"))
    )
    (net (code "73") (name "Net-(U2A-OUT)") (class "Default")
      (node (ref "C14") (pin "2") (pinfunction "2_2") (pintype "passive"))
      (node (ref "Q3") (pin "B") (pinfunction "B_B") (pintype "passive"))
      (node (ref "R19") (pin "2") (pinfunction "2_2") (pintype "passive"))
      (node (ref "U2") (pin "1") (pinfunction "OUT_1") (pintype "output"))
    )
    (net (code "74") (name "Net-(U2B--IN)") (class "Default")
      (node (ref "C4") (pin "2") (pinfunction "2_2") (pintype "passive"))
      (node (ref "Q4") (pin "C") (pinfunction "C_C") (pintype "passive"))
      (node (ref "R20") (pin "2") (pinfunction "2_2") (pintype "passive"))
      (node (ref "U2") (pin "6") (pinfunction "-IN_6") (pintype "input"))
    )
    (net (code "75") (name "Net-(U2B-OUT)") (class "Default")
      (node (ref "C4") (pin "1") (pinfunction "1_1") (pintype "passive"))
      (node (ref "R14") (pin "1") (pinfunction "1_1") (pintype "passive"))
      (node (ref "U2") (pin "7") (pinfunction "OUT_7") (pintype "output"))
    )
    (net (code "76") (name "Net-(U4-(ADC4{slash}SDA{slash}PCINT12)PC4)") (class "Default")
      (node (ref "R36") (pin "2") (pinfunction "2_2") (pintype "passive"))
      (node (ref "U4") (pin "27") (pinfunction "(ADC4/SDA/PCINT12)PC4_27") (pintype "bidirectional"))
    )
    (net (code "77") (name "Net-(U4-(ADC5{slash}SCL{slash}PCINT13)PC5)") (class "Default")
      (node (ref "R35") (pin "2") (pinfunction "2_2") (pintype "passive"))
      (node (ref "U4") (pin "28") (pinfunction "(ADC5/SCL/PCINT13)PC5_28") (pintype "bidirectional"))
    )
    (net (code "78") (name "Net-(U4-(PCINT6{slash}XTAL1{slash}TOSC1)PB6)") (class "Default")
      (node (ref "C27") (pin "2") (pinfunction "2_2") (pintype "passive"))
      (node (ref "Q5") (pin "1") (pinfunction "1_1") (pintype "passive"))
      (node (ref "U4") (pin "7") (pinfunction "(PCINT6/XTAL1/TOSC1)PB6_7") (pintype "bidirectional"))
    )
    (net (code "79") (name "Net-(U4-(PCINT7{slash}XTAL2{slash}TOSC2)PB7)") (class "Default")
      (node (ref "C26") (pin "2") (pinfunction "2_2") (pintype "passive"))
      (node (ref "Q5") (pin "2") (pinfunction "2_2") (pintype "passive"))
      (node (ref "U4") (pin "8") (pinfunction "(PCINT7/XTAL2/TOSC2)PB7_8") (pintype "bidirectional"))
    )
    (net (code "80") (name "VCC") (class "Default")
      (node (ref "C11") (pin "+") (pinfunction "+_+") (pintype "passive"))
      (node (ref "C13") (pin "1") (pinfunction "1_1") (pintype "passive"))
      (node (ref "C17") (pin "1") (pinfunction "1_1") (pintype "passive"))
      (node (ref "C29") (pin "1") (pinfunction "1_1") (pintype "passive"))
      (node (ref "C36") (pin "1") (pinfunction "1_1") (pintype "passive"))
      (node (ref "C6") (pin "1") (pinfunction "1_1") (pintype "passive"))
      (node (ref "C8") (pin "1") (pinfunction "1_1") (pintype "passive"))
      (node (ref "C9") (pin "1") (pinfunction "1_1") (pintype "passive"))
      (node (ref "IC1") (pin "16") (pinfunction "VCC_16") (pintype "power_in"))
      (node (ref "IC2") (pin "11") (pinfunction "V+_11") (pintype "power_in"))
      (node (ref "IC3") (pin "11") (pinfunction "V+_11") (pintype "power_in"))
      (node (ref "IC4") (pin "11") (pinfunction "V+_11") (pintype "power_in"))
      (node (ref "IC5") (pin "8") (pinfunction "V+_8") (pintype "power_in"))
      (node (ref "JP2") (pin "4") (pinfunction "4_4") (pintype "passive"))
      (node (ref "R53") (pin "1") (pinfunction "1_1") (pintype "passive"))
      (node (ref "R54") (pin "1") (pinfunction "1_1") (pintype "passive"))
      (node (ref "U1") (pin "8") (pinfunction "V+_8") (pintype "power_in"))
      (node (ref "U2") (pin "8") (pinfunction "V+_8") (pintype "power_in"))
    )
    (net (code "81") (name "VEE") (class "Default")
      (node (ref "C16") (pin "2") (pinfunction "2_2") (pintype "passive"))
      (node (ref "C18") (pin "2") (pinfunction "2_2") (pintype "passive"))
      (node (ref "C19") (pin "2") (pinfunction "2_2") (pintype "passive"))
      (node (ref "C20") (pin "-") (pinfunction "-_-") (pintype "passive"))
      (node (ref "C3") (pin "2") (pinfunction "2_2") (pintype "passive"))
      (node (ref "C30") (pin "2") (pinfunction "2_2") (pintype "passive"))
      (node (ref "C34") (pin "2") (pinfunction "2_2") (pintype "passive"))
      (node (ref "C37") (pin "2") (pinfunction "2_2") (pintype "passive"))
      (node (ref "IC1") (pin "7") (pinfunction "VEE_7") (pintype "power_in"))
      (node (ref "IC2") (pin "6") (pinfunction "V-_6") (pintype "power_in"))
      (node (ref "IC3") (pin "6") (pinfunction "V-_6") (pintype "power_in"))
      (node (ref "IC4") (pin "6") (pinfunction "V-_6") (pintype "power_in"))
      (node (ref "IC5") (pin "4") (pinfunction "V-_4") (pintype "power_in"))
      (node (ref "JP2") (pin "2") (pinfunction "2_2") (pintype "passive"))
      (node (ref "R10") (pin "1") (pinfunction "1_1") (pintype "passive"))
      (node (ref "R24") (pin "1") (pinfunction "1_1") (pintype "passive"))
      (node (ref "R28") (pin "1") (pinfunction "1_1") (pintype "passive"))
      (node (ref "R40") (pin "2") (pinfunction "2_2") (pintype "passive"))
      (node (ref "R6") (pin "1") (pinfunction "1_1") (pintype "passive"))
      (node (ref "U1") (pin "4") (pinfunction "V-_4") (pintype "power_in"))
      (node (ref "U2") (pin "4") (pinfunction "V-_4") (pintype "power_in"))
    )
    (net (code "82") (name "unconnected-(IC2C-I_DIODE-Pad2)") (class "Default")
      (node (ref "IC2") (pin "2") (pinfunction "I_DIODE_2") (pintype "input"))
    )
    (net (code "83") (name "unconnected-(IC2D-I_DIODE-Pad15)") (class "Default")
      (node (ref "IC2") (pin "15") (pinfunction "I_DIODE_15") (pintype "input"))
    )
    (net (code "84") (name "unconnected-(IC3C-I_DIODE-Pad2)") (class "Default")
      (node (ref "IC3") (pin "2") (pinfunction "I_DIODE_2") (pintype "input"))
    )
    (net (code "85") (name "unconnected-(IC3D-I_DIODE-Pad15)") (class "Default")
      (node (ref "IC3") (pin "15") (pinfunction "I_DIODE_15") (pintype "input"))
    )
    (net (code "86") (name "unconnected-(IC4A-B-Pad7)") (class "Default")
      (node (ref "IC4") (pin "7") (pinfunction "B_7") (pintype "passive"))
    )
    (net (code "87") (name "unconnected-(IC4A-E-Pad8)") (class "Default")
      (node (ref "IC4") (pin "8") (pinfunction "E_8") (pintype "passive"))
    )
    (net (code "88") (name "unconnected-(IC4B-B-Pad10)") (class "Default")
      (node (ref "IC4") (pin "10") (pinfunction "B_10") (pintype "passive"))
    )
    (net (code "89") (name "unconnected-(IC4B-E-Pad9)") (class "Default")
      (node (ref "IC4") (pin "9") (pinfunction "E_9") (pintype "passive"))
    )
    (net (code "90") (name "unconnected-(IC4C-I_DIODE-Pad2)") (class "Default")
      (node (ref "IC4") (pin "2") (pinfunction "I_DIODE_2") (pintype "input"))
    )
    (net (code "91") (name "unconnected-(IC4D-I_DIODE-Pad15)") (class "Default")
      (node (ref "IC4") (pin "15") (pinfunction "I_DIODE_15") (pintype "input"))
    )
    (net (code "92") (name "unconnected-(U4-(ADC2{slash}PCINT10)PC2-Pad25)") (class "Default")
      (node (ref "U4") (pin "25") (pinfunction "(ADC2/PCINT10)PC2_25") (pintype "bidirectional"))
    )
    (net (code "93") (name "unconnected-(U4-(ADC3{slash}PCINT11)PC3-Pad26)") (class "Default")
      (node (ref "U4") (pin "26") (pinfunction "(ADC3/PCINT11)PC3_26") (pintype "bidirectional"))
    )
    (net (code "94") (name "unconnected-(U4-ADC6-Pad19)") (class "Default")
      (node (ref "U4") (pin "19") (pinfunction "ADC6_19") (pintype "input"))
    )
    (net (code "95") (name "unconnected-(U4-ADC7-Pad22)") (class "Default")
      (node (ref "U4") (pin "22") (pinfunction "ADC7_22") (pintype "input"))
    )
    (net (code "96") (name "unconnected-(U4-PD0(RXD{slash}PCINT16)-Pad30)") (class "Default")
      (node (ref "U4") (pin "30") (pinfunction "PD0(RXD/PCINT16)_30") (pintype "bidirectional"))
    )
    (net (code "97") (name "unconnected-(U4-PD3(PCINT19{slash}OC2B{slash}INT1)-Pad1)") (class "Default")
      (node (ref "U4") (pin "1") (pinfunction "PD3(PCINT19/OC2B/INT1)_1") (pintype "bidirectional"))
    )
    (net (code "98") (name "unconnected-(U4-PD7(PCINT23{slash}AIN1)-Pad11)") (class "Default")
      (node (ref "U4") (pin "11") (pinfunction "PD7(PCINT23/AIN1)_11") (pintype "bidirectional"))
    )
  )
)
